# TriggerBoard.net
KiCad netlist of a schematic drawn in EAGLE
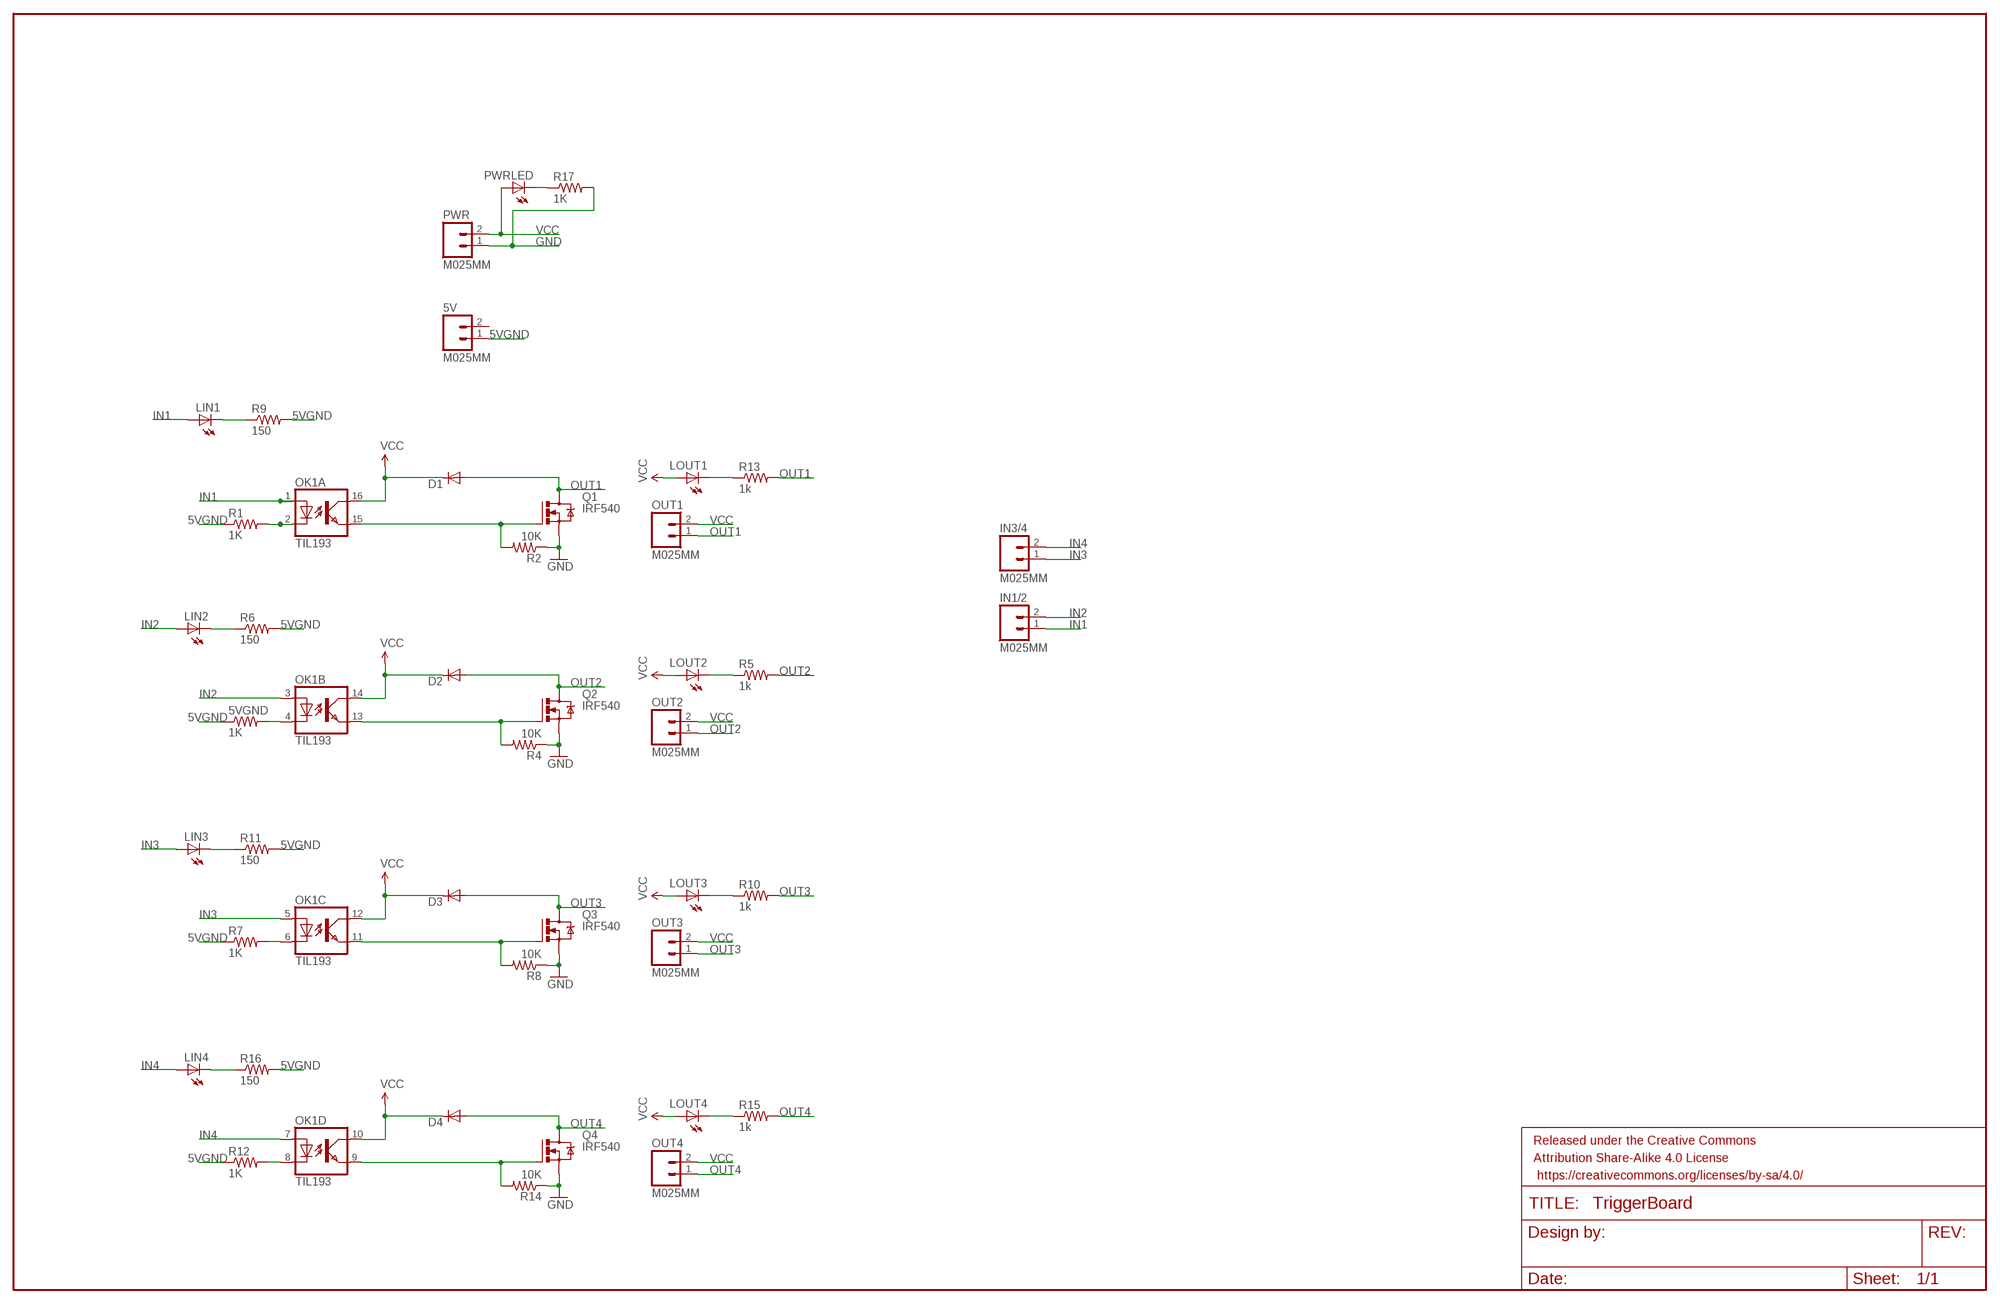
[diagram p0: schematic, sheet 1]

(export (version "E")
  (design (tool "Eeschema 10.0.6"))
  (components
    (comp (ref "5V")
      (value "M025MM")
      (footprint "eagle-import:SCREWTERMINAL-5MM-2")
      (libsource (lib "eagle-import") (part "M025MM"))
    )
    (comp (ref "5VGND")
      (value "1K")
      (footprint "eagle-import:AXIAL-0.4")
      (libsource (lib "eagle-import") (part "RESISTORPTH-1/4W"))
    )
    (comp (ref "D1")
      (value "DIODEPTH")
      (footprint "eagle-import:DIODE-1N4001")
      (libsource (lib "eagle-import") (part "DIODEPTH"))
    )
    (comp (ref "D2")
      (value "DIODEPTH")
      (footprint "eagle-import:DIODE-1N4001")
      (libsource (lib "eagle-import") (part "DIODEPTH"))
    )
    (comp (ref "D3")
      (value "DIODEPTH")
      (footprint "eagle-import:DIODE-1N4001")
      (libsource (lib "eagle-import") (part "DIODEPTH"))
    )
    (comp (ref "D4")
      (value "DIODEPTH")
      (footprint "eagle-import:DIODE-1N4001")
      (libsource (lib "eagle-import") (part "DIODEPTH"))
    )
    (comp (ref "FRAME1")
      (value "FRAME-LEDGER")
      (footprint "eagle-import:CREATIVE_COMMONS")
      (libsource (lib "eagle-import") (part "FRAME-LEDGER"))
    )
    (comp (ref "IN1/2")
      (value "M025MM")
      (footprint "eagle-import:SCREWTERMINAL-5MM-2")
      (libsource (lib "eagle-import") (part "M025MM"))
    )
    (comp (ref "IN3/4")
      (value "M025MM")
      (footprint "eagle-import:SCREWTERMINAL-5MM-2")
      (libsource (lib "eagle-import") (part "M025MM"))
    )
    (comp (ref "LIN1")
      (value "LED3MM")
      (footprint "eagle-import:LED3MM")
      (libsource (lib "eagle-import") (part "LED3MM"))
    )
    (comp (ref "LIN2")
      (value "LED3MM")
      (footprint "eagle-import:LED3MM")
      (libsource (lib "eagle-import") (part "LED3MM"))
    )
    (comp (ref "LIN3")
      (value "LED3MM")
      (footprint "eagle-import:LED3MM")
      (libsource (lib "eagle-import") (part "LED3MM"))
    )
    (comp (ref "LIN4")
      (value "LED3MM")
      (footprint "eagle-import:LED3MM")
      (libsource (lib "eagle-import") (part "LED3MM"))
    )
    (comp (ref "LOUT1")
      (value "LED3MM")
      (footprint "eagle-import:LED3MM")
      (libsource (lib "eagle-import") (part "LED3MM"))
    )
    (comp (ref "LOUT2")
      (value "LED3MM")
      (footprint "eagle-import:LED3MM")
      (libsource (lib "eagle-import") (part "LED3MM"))
    )
    (comp (ref "LOUT3")
      (value "LED3MM")
      (footprint "eagle-import:LED3MM")
      (libsource (lib "eagle-import") (part "LED3MM"))
    )
    (comp (ref "LOUT4")
      (value "LED3MM")
      (footprint "eagle-import:LED3MM")
      (libsource (lib "eagle-import") (part "LED3MM"))
    )
    (comp (ref "OK1")
      (value "TIL193")
      (footprint "eagle-import:DIL16")
      (libsource (lib "eagle-import") (part "TIL193"))
    )
    (comp (ref "OUT1")
      (value "M025MM")
      (footprint "eagle-import:SCREWTERMINAL-5MM-2")
      (libsource (lib "eagle-import") (part "M025MM"))
    )
    (comp (ref "OUT2")
      (value "M025MM")
      (footprint "eagle-import:SCREWTERMINAL-5MM-2")
      (libsource (lib "eagle-import") (part "M025MM"))
    )
    (comp (ref "OUT3")
      (value "M025MM")
      (footprint "eagle-import:SCREWTERMINAL-5MM-2")
      (libsource (lib "eagle-import") (part "M025MM"))
    )
    (comp (ref "OUT4")
      (value "M025MM")
      (footprint "eagle-import:SCREWTERMINAL-5MM-2")
      (libsource (lib "eagle-import") (part "M025MM"))
    )
    (comp (ref "PWR")
      (value "M025MM")
      (footprint "eagle-import:SCREWTERMINAL-5MM-2")
      (libsource (lib "eagle-import") (part "M025MM"))
    )
    (comp (ref "PWRLED")
      (value "LED5MM")
      (footprint "eagle-import:LED5MM")
      (libsource (lib "eagle-import") (part "LED5MM"))
    )
    (comp (ref "Q1")
      (value "IRF540")
      (footprint "eagle-import:TO220BV")
      (libsource (lib "eagle-import") (part "IRF540"))
    )
    (comp (ref "Q2")
      (value "IRF540")
      (footprint "eagle-import:TO220BV")
      (libsource (lib "eagle-import") (part "IRF540"))
    )
    (comp (ref "Q3")
      (value "IRF540")
      (footprint "eagle-import:TO220BV")
      (libsource (lib "eagle-import") (part "IRF540"))
    )
    (comp (ref "Q4")
      (value "IRF540")
      (footprint "eagle-import:TO220BV")
      (libsource (lib "eagle-import") (part "IRF540"))
    )
    (comp (ref "R1")
      (value "1K")
      (footprint "eagle-import:AXIAL-0.4")
      (libsource (lib "eagle-import") (part "RESISTORPTH-1/4W"))
    )
    (comp (ref "R2")
      (value "10K")
      (footprint "eagle-import:AXIAL-0.4")
      (libsource (lib "eagle-import") (part "RESISTORPTH-1/4W"))
    )
    (comp (ref "R4")
      (value "10K")
      (footprint "eagle-import:AXIAL-0.4")
      (libsource (lib "eagle-import") (part "RESISTORPTH-1/4W"))
    )
    (comp (ref "R5")
      (value "1k")
      (footprint "eagle-import:AXIAL-0.4")
      (libsource (lib "eagle-import") (part "RESISTORPTH-1/4W"))
    )
    (comp (ref "R6")
      (value "150")
      (footprint "eagle-import:AXIAL-0.4")
      (libsource (lib "eagle-import") (part "RESISTORPTH-1/4W"))
    )
    (comp (ref "R7")
      (value "1K")
      (footprint "eagle-import:AXIAL-0.4")
      (libsource (lib "eagle-import") (part "RESISTORPTH-1/4W"))
    )
    (comp (ref "R8")
      (value "10K")
      (footprint "eagle-import:AXIAL-0.4")
      (libsource (lib "eagle-import") (part "RESISTORPTH-1/4W"))
    )
    (comp (ref "R9")
      (value "150")
      (footprint "eagle-import:AXIAL-0.4")
      (libsource (lib "eagle-import") (part "RESISTORPTH-1/4W"))
    )
    (comp (ref "R10")
      (value "1k")
      (footprint "eagle-import:AXIAL-0.4")
      (libsource (lib "eagle-import") (part "RESISTORPTH-1/4W"))
    )
    (comp (ref "R11")
      (value "150")
      (footprint "eagle-import:AXIAL-0.4")
      (libsource (lib "eagle-import") (part "RESISTORPTH-1/4W"))
    )
    (comp (ref "R12")
      (value "1K")
      (footprint "eagle-import:AXIAL-0.4")
      (libsource (lib "eagle-import") (part "RESISTORPTH-1/4W"))
    )
    (comp (ref "R13")
      (value "1k")
      (footprint "eagle-import:AXIAL-0.4")
      (libsource (lib "eagle-import") (part "RESISTORPTH-1/4W"))
    )
    (comp (ref "R14")
      (value "10K")
      (footprint "eagle-import:AXIAL-0.4")
      (libsource (lib "eagle-import") (part "RESISTORPTH-1/4W"))
    )
    (comp (ref "R15")
      (value "1k")
      (footprint "eagle-import:AXIAL-0.4")
      (libsource (lib "eagle-import") (part "RESISTORPTH-1/4W"))
    )
    (comp (ref "R16")
      (value "150")
      (footprint "eagle-import:AXIAL-0.4")
      (libsource (lib "eagle-import") (part "RESISTORPTH-1/4W"))
    )
    (comp (ref "R17")
      (value "1K")
      (footprint "eagle-import:AXIAL-0.4")
      (libsource (lib "eagle-import") (part "RESISTORPTH-1/4W"))
    )
  )
  (nets
    (net (code "1") (name "/5VGND") (class "Default")
      (node (ref "5V") (pin "1") (pinfunction "1_1") (pintype "passive"))
      (node (ref "5VGND") (pin "P$1") (pinfunction "1_P$1") (pintype "passive"))
      (node (ref "R1") (pin "P$1") (pinfunction "1_P$1") (pintype "passive"))
      (node (ref "R11") (pin "P$2") (pinfunction "2_P$2") (pintype "passive"))
      (node (ref "R12") (pin "P$1") (pinfunction "1_P$1") (pintype "passive"))
      (node (ref "R16") (pin "P$2") (pinfunction "2_P$2") (pintype "passive"))
      (node (ref "R6") (pin "P$2") (pinfunction "2_P$2") (pintype "passive"))
      (node (ref "R7") (pin "P$1") (pinfunction "1_P$1") (pintype "passive"))
      (node (ref "R9") (pin "P$2") (pinfunction "2_P$2") (pintype "passive"))
    )
    (net (code "2") (name "/IN1") (class "Default")
      (node (ref "IN1/2") (pin "1") (pinfunction "1_1") (pintype "passive"))
      (node (ref "LIN1") (pin "A") (pinfunction "A_A") (pintype "passive"))
      (node (ref "OK1") (pin "1") (pinfunction "A_1") (pintype "passive"))
    )
    (net (code "3") (name "/IN2") (class "Default")
      (node (ref "IN1/2") (pin "2") (pinfunction "2_2") (pintype "passive"))
      (node (ref "LIN2") (pin "A") (pinfunction "A_A") (pintype "passive"))
      (node (ref "OK1") (pin "3") (pinfunction "A_3") (pintype "passive"))
    )
    (net (code "4") (name "/IN3") (class "Default")
      (node (ref "IN3/4") (pin "1") (pinfunction "1_1") (pintype "passive"))
      (node (ref "LIN3") (pin "A") (pinfunction "A_A") (pintype "passive"))
      (node (ref "OK1") (pin "5") (pinfunction "A_5") (pintype "passive"))
    )
    (net (code "5") (name "/IN4") (class "Default")
      (node (ref "IN3/4") (pin "2") (pinfunction "2_2") (pintype "passive"))
      (node (ref "LIN4") (pin "A") (pinfunction "A_A") (pintype "passive"))
      (node (ref "OK1") (pin "7") (pinfunction "A_7") (pintype "passive"))
    )
    (net (code "6") (name "/OUT1") (class "Default")
      (node (ref "D1") (pin "A") (pinfunction "A_A") (pintype "passive"))
      (node (ref "OUT1") (pin "1") (pinfunction "1_1") (pintype "passive"))
      (node (ref "Q1") (pin "D") (pinfunction "D_D") (pintype "passive"))
      (node (ref "R13") (pin "P$2") (pinfunction "2_P$2") (pintype "passive"))
    )
    (net (code "7") (name "/OUT2") (class "Default")
      (node (ref "D2") (pin "A") (pinfunction "A_A") (pintype "passive"))
      (node (ref "OUT2") (pin "1") (pinfunction "1_1") (pintype "passive"))
      (node (ref "Q2") (pin "D") (pinfunction "D_D") (pintype "passive"))
      (node (ref "R5") (pin "P$2") (pinfunction "2_P$2") (pintype "passive"))
    )
    (net (code "8") (name "/OUT3") (class "Default")
      (node (ref "D3") (pin "A") (pinfunction "A_A") (pintype "passive"))
      (node (ref "OUT3") (pin "1") (pinfunction "1_1") (pintype "passive"))
      (node (ref "Q3") (pin "D") (pinfunction "D_D") (pintype "passive"))
      (node (ref "R10") (pin "P$2") (pinfunction "2_P$2") (pintype "passive"))
    )
    (net (code "9") (name "/OUT4") (class "Default")
      (node (ref "D4") (pin "A") (pinfunction "A_A") (pintype "passive"))
      (node (ref "OUT4") (pin "1") (pinfunction "1_1") (pintype "passive"))
      (node (ref "Q4") (pin "D") (pinfunction "D_D") (pintype "passive"))
      (node (ref "R15") (pin "P$2") (pinfunction "2_P$2") (pintype "passive"))
    )
    (net (code "10") (name "GND") (class "Default")
      (node (ref "PWR") (pin "1") (pinfunction "1_1") (pintype "passive"))
      (node (ref "Q1") (pin "S") (pinfunction "S_S") (pintype "passive"))
      (node (ref "Q2") (pin "S") (pinfunction "S_S") (pintype "passive"))
      (node (ref "Q3") (pin "S") (pinfunction "S_S") (pintype "passive"))
      (node (ref "Q4") (pin "S") (pinfunction "S_S") (pintype "passive"))
      (node (ref "R14") (pin "P$1") (pinfunction "1_P$1") (pintype "passive"))
      (node (ref "R17") (pin "P$2") (pinfunction "2_P$2") (pintype "passive"))
      (node (ref "R2") (pin "P$1") (pinfunction "1_P$1") (pintype "passive"))
      (node (ref "R4") (pin "P$1") (pinfunction "1_P$1") (pintype "passive"))
      (node (ref "R8") (pin "P$1") (pinfunction "1_P$1") (pintype "passive"))
    )
    (net (code "11") (name "Net-(5VGND-2)") (class "Default")
      (node (ref "5VGND") (pin "P$2") (pinfunction "2_P$2") (pintype "passive"))
      (node (ref "OK1") (pin "4") (pinfunction "C_4") (pintype "passive"))
    )
    (net (code "12") (name "Net-(LIN1-C)") (class "Default")
      (node (ref "LIN1") (pin "K") (pinfunction "C_K") (pintype "passive"))
      (node (ref "R9") (pin "P$1") (pinfunction "1_P$1") (pintype "passive"))
    )
    (net (code "13") (name "Net-(LIN2-C)") (class "Default")
      (node (ref "LIN2") (pin "K") (pinfunction "C_K") (pintype "passive"))
      (node (ref "R6") (pin "P$1") (pinfunction "1_P$1") (pintype "passive"))
    )
    (net (code "14") (name "Net-(LIN3-C)") (class "Default")
      (node (ref "LIN3") (pin "K") (pinfunction "C_K") (pintype "passive"))
      (node (ref "R11") (pin "P$1") (pinfunction "1_P$1") (pintype "passive"))
    )
    (net (code "15") (name "Net-(LIN4-C)") (class "Default")
      (node (ref "LIN4") (pin "K") (pinfunction "C_K") (pintype "passive"))
      (node (ref "R16") (pin "P$1") (pinfunction "1_P$1") (pintype "passive"))
    )
    (net (code "16") (name "Net-(LOUT1-C)") (class "Default")
      (node (ref "LOUT1") (pin "K") (pinfunction "C_K") (pintype "passive"))
      (node (ref "R13") (pin "P$1") (pinfunction "1_P$1") (pintype "passive"))
    )
    (net (code "17") (name "Net-(LOUT2-C)") (class "Default")
      (node (ref "LOUT2") (pin "K") (pinfunction "C_K") (pintype "passive"))
      (node (ref "R5") (pin "P$1") (pinfunction "1_P$1") (pintype "passive"))
    )
    (net (code "18") (name "Net-(LOUT3-C)") (class "Default")
      (node (ref "LOUT3") (pin "K") (pinfunction "C_K") (pintype "passive"))
      (node (ref "R10") (pin "P$1") (pinfunction "1_P$1") (pintype "passive"))
    )
    (net (code "19") (name "Net-(LOUT4-C)") (class "Default")
      (node (ref "LOUT4") (pin "K") (pinfunction "C_K") (pintype "passive"))
      (node (ref "R15") (pin "P$1") (pinfunction "1_P$1") (pintype "passive"))
    )
    (net (code "20") (name "Net-(OK1A-C)") (class "Default")
      (node (ref "OK1") (pin "2") (pinfunction "C_2") (pintype "passive"))
      (node (ref "R1") (pin "P$2") (pinfunction "2_P$2") (pintype "passive"))
    )
    (net (code "21") (name "Net-(OK1A-EMIT)") (class "Default")
      (node (ref "OK1") (pin "15") (pinfunction "EMIT_15") (pintype "passive"))
      (node (ref "Q1") (pin "G") (pinfunction "G_G") (pintype "passive"))
      (node (ref "R2") (pin "P$2") (pinfunction "2_P$2") (pintype "passive"))
    )
    (net (code "22") (name "Net-(OK1B-EMIT)") (class "Default")
      (node (ref "OK1") (pin "13") (pinfunction "EMIT_13") (pintype "passive"))
      (node (ref "Q2") (pin "G") (pinfunction "G_G") (pintype "passive"))
      (node (ref "R4") (pin "P$2") (pinfunction "2_P$2") (pintype "passive"))
    )
    (net (code "23") (name "Net-(OK1C-C)") (class "Default")
      (node (ref "OK1") (pin "6") (pinfunction "C_6") (pintype "passive"))
      (node (ref "R7") (pin "P$2") (pinfunction "2_P$2") (pintype "passive"))
    )
    (net (code "24") (name "Net-(OK1C-EMIT)") (class "Default")
      (node (ref "OK1") (pin "11") (pinfunction "EMIT_11") (pintype "passive"))
      (node (ref "Q3") (pin "G") (pinfunction "G_G") (pintype "passive"))
      (node (ref "R8") (pin "P$2") (pinfunction "2_P$2") (pintype "passive"))
    )
    (net (code "25") (name "Net-(OK1D-C)") (class "Default")
      (node (ref "OK1") (pin "8") (pinfunction "C_8") (pintype "passive"))
      (node (ref "R12") (pin "P$2") (pinfunction "2_P$2") (pintype "passive"))
    )
    (net (code "26") (name "Net-(OK1D-EMIT)") (class "Default")
      (node (ref "OK1") (pin "9") (pinfunction "EMIT_9") (pintype "passive"))
      (node (ref "Q4") (pin "G") (pinfunction "G_G") (pintype "passive"))
      (node (ref "R14") (pin "P$2") (pinfunction "2_P$2") (pintype "passive"))
    )
    (net (code "27") (name "Net-(PWRLED-C)") (class "Default")
      (node (ref "PWRLED") (pin "K") (pinfunction "C_K") (pintype "passive"))
      (node (ref "R17") (pin "P$1") (pinfunction "1_P$1") (pintype "passive"))
    )
    (net (code "28") (name "VCC") (class "Default")
      (node (ref "D1") (pin "C") (pinfunction "C_C") (pintype "passive"))
      (node (ref "D2") (pin "C") (pinfunction "C_C") (pintype "passive"))
      (node (ref "D3") (pin "C") (pinfunction "C_C") (pintype "passive"))
      (node (ref "D4") (pin "C") (pinfunction "C_C") (pintype "passive"))
      (node (ref "LOUT1") (pin "A") (pinfunction "A_A") (pintype "passive"))
      (node (ref "LOUT2") (pin "A") (pinfunction "A_A") (pintype "passive"))
      (node (ref "LOUT3") (pin "A") (pinfunction "A_A") (pintype "passive"))
      (node (ref "LOUT4") (pin "A") (pinfunction "A_A") (pintype "passive"))
      (node (ref "OK1") (pin "10") (pinfunction "COL_10") (pintype "passive"))
      (node (ref "OK1") (pin "12") (pinfunction "COL_12") (pintype "passive"))
      (node (ref "OK1") (pin "14") (pinfunction "COL_14") (pintype "passive"))
      (node (ref "OK1") (pin "16") (pinfunction "COL_16") (pintype "passive"))
      (node (ref "OUT1") (pin "2") (pinfunction "2_2") (pintype "passive"))
      (node (ref "OUT2") (pin "2") (pinfunction "2_2") (pintype "passive"))
      (node (ref "OUT3") (pin "2") (pinfunction "2_2") (pintype "passive"))
      (node (ref "OUT4") (pin "2") (pinfunction "2_2") (pintype "passive"))
      (node (ref "PWR") (pin "2") (pinfunction "2_2") (pintype "passive"))
      (node (ref "PWRLED") (pin "A") (pinfunction "A_A") (pintype "passive"))
    )
    (net (code "29") (name "unconnected-(5V-Pad2)") (class "Default")
      (node (ref "5V") (pin "2") (pinfunction "2_2") (pintype "passive"))
    )
  )
)
